# switch_v4.net
KiCad netlist of a schematic drawn in EAGLE
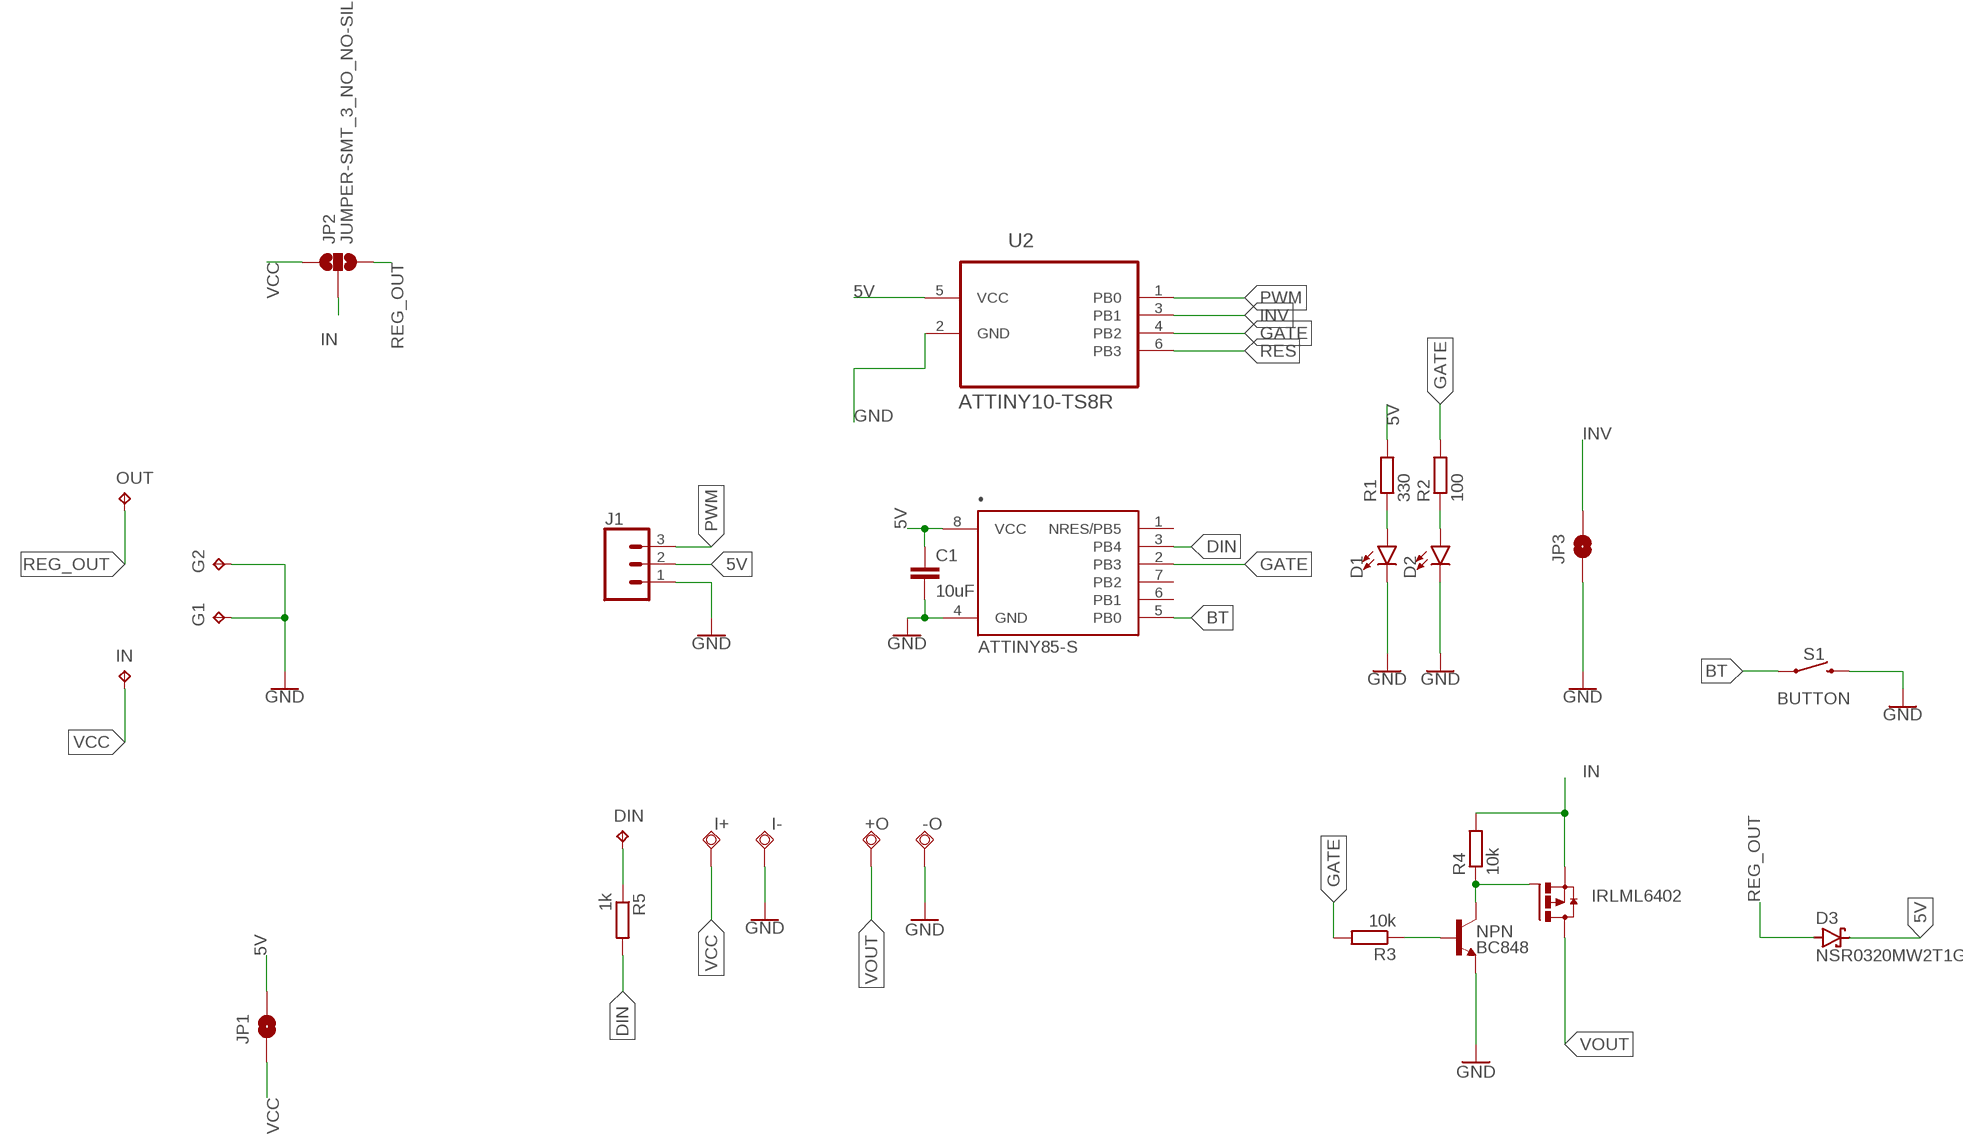
[diagram p0: schematic, sheet 1]

(export (version "E")
  (design (tool "Eeschema 10.0.6"))
  (components
    (comp (ref "+O")
      (value "TPSQTP20SQ")
      (footprint "eagle-import:TP20SQ")
      (libsource (lib "eagle-import") (part "TPSQTP20SQ"))
    )
    (comp (ref "-O")
      (value "TPSQTP20SQ")
      (footprint "eagle-import:TP20SQ")
      (libsource (lib "eagle-import") (part "TPSQTP20SQ"))
    )
    (comp (ref "C1")
      (value "10uF")
      (footprint "eagle-import:C0603K")
      (libsource (lib "eagle-import") (part "C-EUC0603K"))
    )
    (comp (ref "D1")
      (value "LED0603")
      (footprint "eagle-import:LED-0603")
      (libsource (lib "eagle-import") (part "LED0603"))
    )
    (comp (ref "D2")
      (value "LED0603")
      (footprint "eagle-import:LED-0603")
      (libsource (lib "eagle-import") (part "LED0603"))
    )
    (comp (ref "D3")
      (value "NSR0320MW2T1G")
      (footprint "eagle-import:SOD323_ST")
      (libsource (lib "eagle-import") (part "BAT60J"))
    )
    (comp (ref "DIN")
      (value "TPTP15R")
      (footprint "eagle-import:TP15R")
      (libsource (lib "eagle-import") (part "TPTP15R"))
    )
    (comp (ref "G1")
      (value "TPTP15R")
      (footprint "eagle-import:TP15R")
      (libsource (lib "eagle-import") (part "TPTP15R"))
    )
    (comp (ref "G2")
      (value "TPTP15R")
      (footprint "eagle-import:TP15R")
      (libsource (lib "eagle-import") (part "TPTP15R"))
    )
    (comp (ref "I+")
      (value "TPSQTP20SQ")
      (footprint "eagle-import:TP20SQ")
      (libsource (lib "eagle-import") (part "TPSQTP20SQ"))
    )
    (comp (ref "I-")
      (value "TPSQTP20SQ")
      (footprint "eagle-import:TP20SQ")
      (libsource (lib "eagle-import") (part "TPSQTP20SQ"))
    )
    (comp (ref "IN")
      (value "TPTP15R")
      (footprint "eagle-import:TP15R")
      (libsource (lib "eagle-import") (part "TPTP15R"))
    )
    (comp (ref "IRLML6402")
      (value "FDN360P")
      (footprint "eagle-import:SUPER-SOT3")
      (libsource (lib "eagle-import") (part "FDN360P"))
    )
    (comp (ref "J1")
      (value "CONN_03")
      (footprint "eagle-import:1X03")
      (libsource (lib "eagle-import") (part "CONN_03"))
    )
    (comp (ref "JP1")
      (value "JUMPER-SMT_2_NO_NO-SILK")
      (footprint "eagle-import:SMT-JUMPER_2_NO_NO-SILK")
      (libsource (lib "eagle-import") (part "JUMPER-SMT_2_NO_NO-SILK"))
    )
    (comp (ref "JP2")
      (value "JUMPER-SMT_3_NO_NO-SILK")
      (footprint "eagle-import:SMT-JUMPER_3_NO_NO-SILK")
      (libsource (lib "eagle-import") (part "JUMPER-SMT_3_NO_NO-SILK"))
    )
    (comp (ref "JP3")
      (value "JUMPER-SMT_2_NO_NO-SILK")
      (footprint "eagle-import:SMT-JUMPER_2_NO_NO-SILK")
      (libsource (lib "eagle-import") (part "JUMPER-SMT_2_NO_NO-SILK"))
    )
    (comp (ref "NPN")
      (value "BC848")
      (footprint "eagle-import:SOT23-3")
      (libsource (lib "eagle-import") (part "TRANS_NPN-MMBT2222AL"))
    )
    (comp (ref "OUT")
      (value "TPTP15R")
      (footprint "eagle-import:TP15R")
      (libsource (lib "eagle-import") (part "TPTP15R"))
    )
    (comp (ref "R1")
      (value "330")
      (footprint "eagle-import:R0603")
      (libsource (lib "eagle-import") (part "R-EU_R0603"))
    )
    (comp (ref "R2")
      (value "100")
      (footprint "eagle-import:R0603")
      (libsource (lib "eagle-import") (part "R-EU_R0603"))
    )
    (comp (ref "R3")
      (value "10k")
      (footprint "eagle-import:R0603")
      (libsource (lib "eagle-import") (part "R-EU_R0603"))
    )
    (comp (ref "R4")
      (value "10k")
      (footprint "eagle-import:R0603")
      (libsource (lib "eagle-import") (part "R-EU_R0603"))
    )
    (comp (ref "R5")
      (value "1k")
      (footprint "eagle-import:R0603")
      (libsource (lib "eagle-import") (part "R-EU_R0603"))
    )
    (comp (ref "S1")
      (value "BUTTON")
      (footprint "eagle-import:TACTILE_SWITCH_SMD_4.6X2.8MM")
      (libsource (lib "eagle-import") (part "MOMENTARY-SWITCH-SPST-SMD-4.6X2.8MM"))
    )
    (comp (ref "U2")
      (value "ATTINY10-TS8R")
      (footprint "eagle-import:SOT95P280X145-6N")
      (fields (field (name "MF") "Microchip"))
      (libsource (lib "eagle-import") (part "ATTINY10-TS8R"))
    )
    (comp (ref "•")
      (value "ATTINY85-S")
      (footprint "eagle-import:SOIC8_EIAJ_208MIL")
      (libsource (lib "eagle-import") (part "ATTINY85S-"))
    )
  )
  (nets
    (net (code "1") (name "/IN") (class "Default")
      (node (ref "IRLML6402") (pin "2") (pinfunction "S_2") (pintype "passive"))
      (node (ref "JP2") (pin "2") (pinfunction "2_2") (pintype "passive"))
      (node (ref "R4") (pin "2") (pinfunction "2_2") (pintype "passive"))
    )
    (net (code "2") (name "5V") (class "Default")
      (node (ref "C1") (pin "1") (pinfunction "1_1") (pintype "passive"))
      (node (ref "D3") (pin "C") (pinfunction "C_C") (pintype "passive"))
      (node (ref "J1") (pin "2") (pinfunction "2_2") (pintype "passive"))
      (node (ref "JP1") (pin "2") (pinfunction "2_2") (pintype "passive"))
      (node (ref "R1") (pin "2") (pinfunction "2_2") (pintype "passive"))
      (node (ref "U2") (pin "5") (pinfunction "VCC_5") (pintype "power_in"))
      (node (ref "•") (pin "8") (pinfunction "VCC_8") (pintype "power_in"))
    )
    (net (code "3") (name "BT") (class "Default")
      (node (ref "S1") (pin "1") (pinfunction "1_1") (pintype "passive"))
      (node (ref "S1") (pin "2") (pinfunction "1_2") (pintype "passive"))
      (node (ref "•") (pin "5") (pinfunction "PB0_5") (pintype "bidirectional"))
    )
    (net (code "4") (name "DIN") (class "Default")
      (node (ref "R5") (pin "2") (pinfunction "2_2") (pintype "passive"))
      (node (ref "•") (pin "3") (pinfunction "PB4_3") (pintype "bidirectional"))
    )
    (net (code "5") (name "GATE") (class "Default")
      (node (ref "R2") (pin "2") (pinfunction "2_2") (pintype "passive"))
      (node (ref "R3") (pin "2") (pinfunction "2_2") (pintype "passive"))
      (node (ref "U2") (pin "4") (pinfunction "PB2_4") (pintype "bidirectional"))
      (node (ref "•") (pin "2") (pinfunction "PB3_2") (pintype "bidirectional"))
    )
    (net (code "6") (name "GND") (class "Default")
      (node (ref "-O") (pin "TP") (pinfunction "TP_TP") (pintype "input"))
      (node (ref "C1") (pin "2") (pinfunction "2_2") (pintype "passive"))
      (node (ref "D1") (pin "C") (pinfunction "C_C") (pintype "passive"))
      (node (ref "D2") (pin "C") (pinfunction "C_C") (pintype "passive"))
      (node (ref "G1") (pin "TP") (pinfunction "TP_TP") (pintype "input"))
      (node (ref "G2") (pin "TP") (pinfunction "TP_TP") (pintype "input"))
      (node (ref "I-") (pin "TP") (pinfunction "TP_TP") (pintype "input"))
      (node (ref "J1") (pin "1") (pinfunction "1_1") (pintype "passive"))
      (node (ref "JP3") (pin "1") (pinfunction "1_1") (pintype "passive"))
      (node (ref "NPN") (pin "2") (pinfunction "E_2") (pintype "passive"))
      (node (ref "S1") (pin "3") (pinfunction "2_3") (pintype "passive"))
      (node (ref "S1") (pin "4") (pinfunction "2_4") (pintype "passive"))
      (node (ref "U2") (pin "2") (pinfunction "GND_2") (pintype "passive"))
      (node (ref "•") (pin "4") (pinfunction "GND_4") (pintype "power_in"))
    )
    (net (code "7") (name "INV") (class "Default")
      (node (ref "JP3") (pin "2") (pinfunction "2_2") (pintype "passive"))
      (node (ref "U2") (pin "3") (pinfunction "PB1_3") (pintype "bidirectional"))
    )
    (net (code "8") (name "Net-(D1-PadA)") (class "Default")
      (node (ref "D1") (pin "A") (pinfunction "A_A") (pintype "passive"))
      (node (ref "R1") (pin "1") (pinfunction "1_1") (pintype "passive"))
    )
    (net (code "9") (name "Net-(D2-PadA)") (class "Default")
      (node (ref "D2") (pin "A") (pinfunction "A_A") (pintype "passive"))
      (node (ref "R2") (pin "1") (pinfunction "1_1") (pintype "passive"))
    )
    (net (code "10") (name "Net-(DIN-PadTP)") (class "Default")
      (node (ref "DIN") (pin "TP") (pinfunction "TP_TP") (pintype "input"))
      (node (ref "R5") (pin "1") (pinfunction "1_1") (pintype "passive"))
    )
    (net (code "11") (name "Net-(IRLML6402-G)") (class "Default")
      (node (ref "IRLML6402") (pin "1") (pinfunction "G_1") (pintype "passive"))
      (node (ref "NPN") (pin "3") (pinfunction "C_3") (pintype "passive"))
      (node (ref "R4") (pin "1") (pinfunction "1_1") (pintype "passive"))
    )
    (net (code "12") (name "Net-(NPN-B)") (class "Default")
      (node (ref "NPN") (pin "1") (pinfunction "B_1") (pintype "passive"))
      (node (ref "R3") (pin "1") (pinfunction "1_1") (pintype "passive"))
    )
    (net (code "13") (name "PWM") (class "Default")
      (node (ref "J1") (pin "3") (pinfunction "3_3") (pintype "passive"))
      (node (ref "U2") (pin "1") (pinfunction "PB0_1") (pintype "bidirectional"))
    )
    (net (code "14") (name "REG_OUT") (class "Default")
      (node (ref "D3") (pin "A") (pinfunction "A_A") (pintype "passive"))
      (node (ref "JP2") (pin "3") (pinfunction "3_3") (pintype "passive"))
      (node (ref "OUT") (pin "TP") (pinfunction "TP_TP") (pintype "input"))
    )
    (net (code "15") (name "RES") (class "Default")
      (node (ref "U2") (pin "6") (pinfunction "PB3_6") (pintype "bidirectional"))
    )
    (net (code "16") (name "VCC") (class "Default")
      (node (ref "I+") (pin "TP") (pinfunction "TP_TP") (pintype "input"))
      (node (ref "IN") (pin "TP") (pinfunction "TP_TP") (pintype "input"))
      (node (ref "JP1") (pin "1") (pinfunction "1_1") (pintype "passive"))
      (node (ref "JP2") (pin "1") (pinfunction "1_1") (pintype "passive"))
    )
    (net (code "17") (name "VOUT") (class "Default")
      (node (ref "+O") (pin "TP") (pinfunction "TP_TP") (pintype "input"))
      (node (ref "IRLML6402") (pin "3") (pinfunction "D_3") (pintype "passive"))
    )
    (net (code "18") (name "unconnected-(•-NRES{slash}PB5-Pad1)") (class "Default")
      (node (ref "•") (pin "1") (pinfunction "NRES/PB5_1") (pintype "bidirectional"))
    )
    (net (code "19") (name "unconnected-(•-PB1-Pad6)") (class "Default")
      (node (ref "•") (pin "6") (pinfunction "PB1_6") (pintype "bidirectional"))
    )
    (net (code "20") (name "unconnected-(•-PB2-Pad7)") (class "Default")
      (node (ref "•") (pin "7") (pinfunction "PB2_7") (pintype "bidirectional"))
    )
  )
)
